# 2015_FDP_ACTIONNEUR.net
KiCad netlist of a schematic drawn in Altium Designer
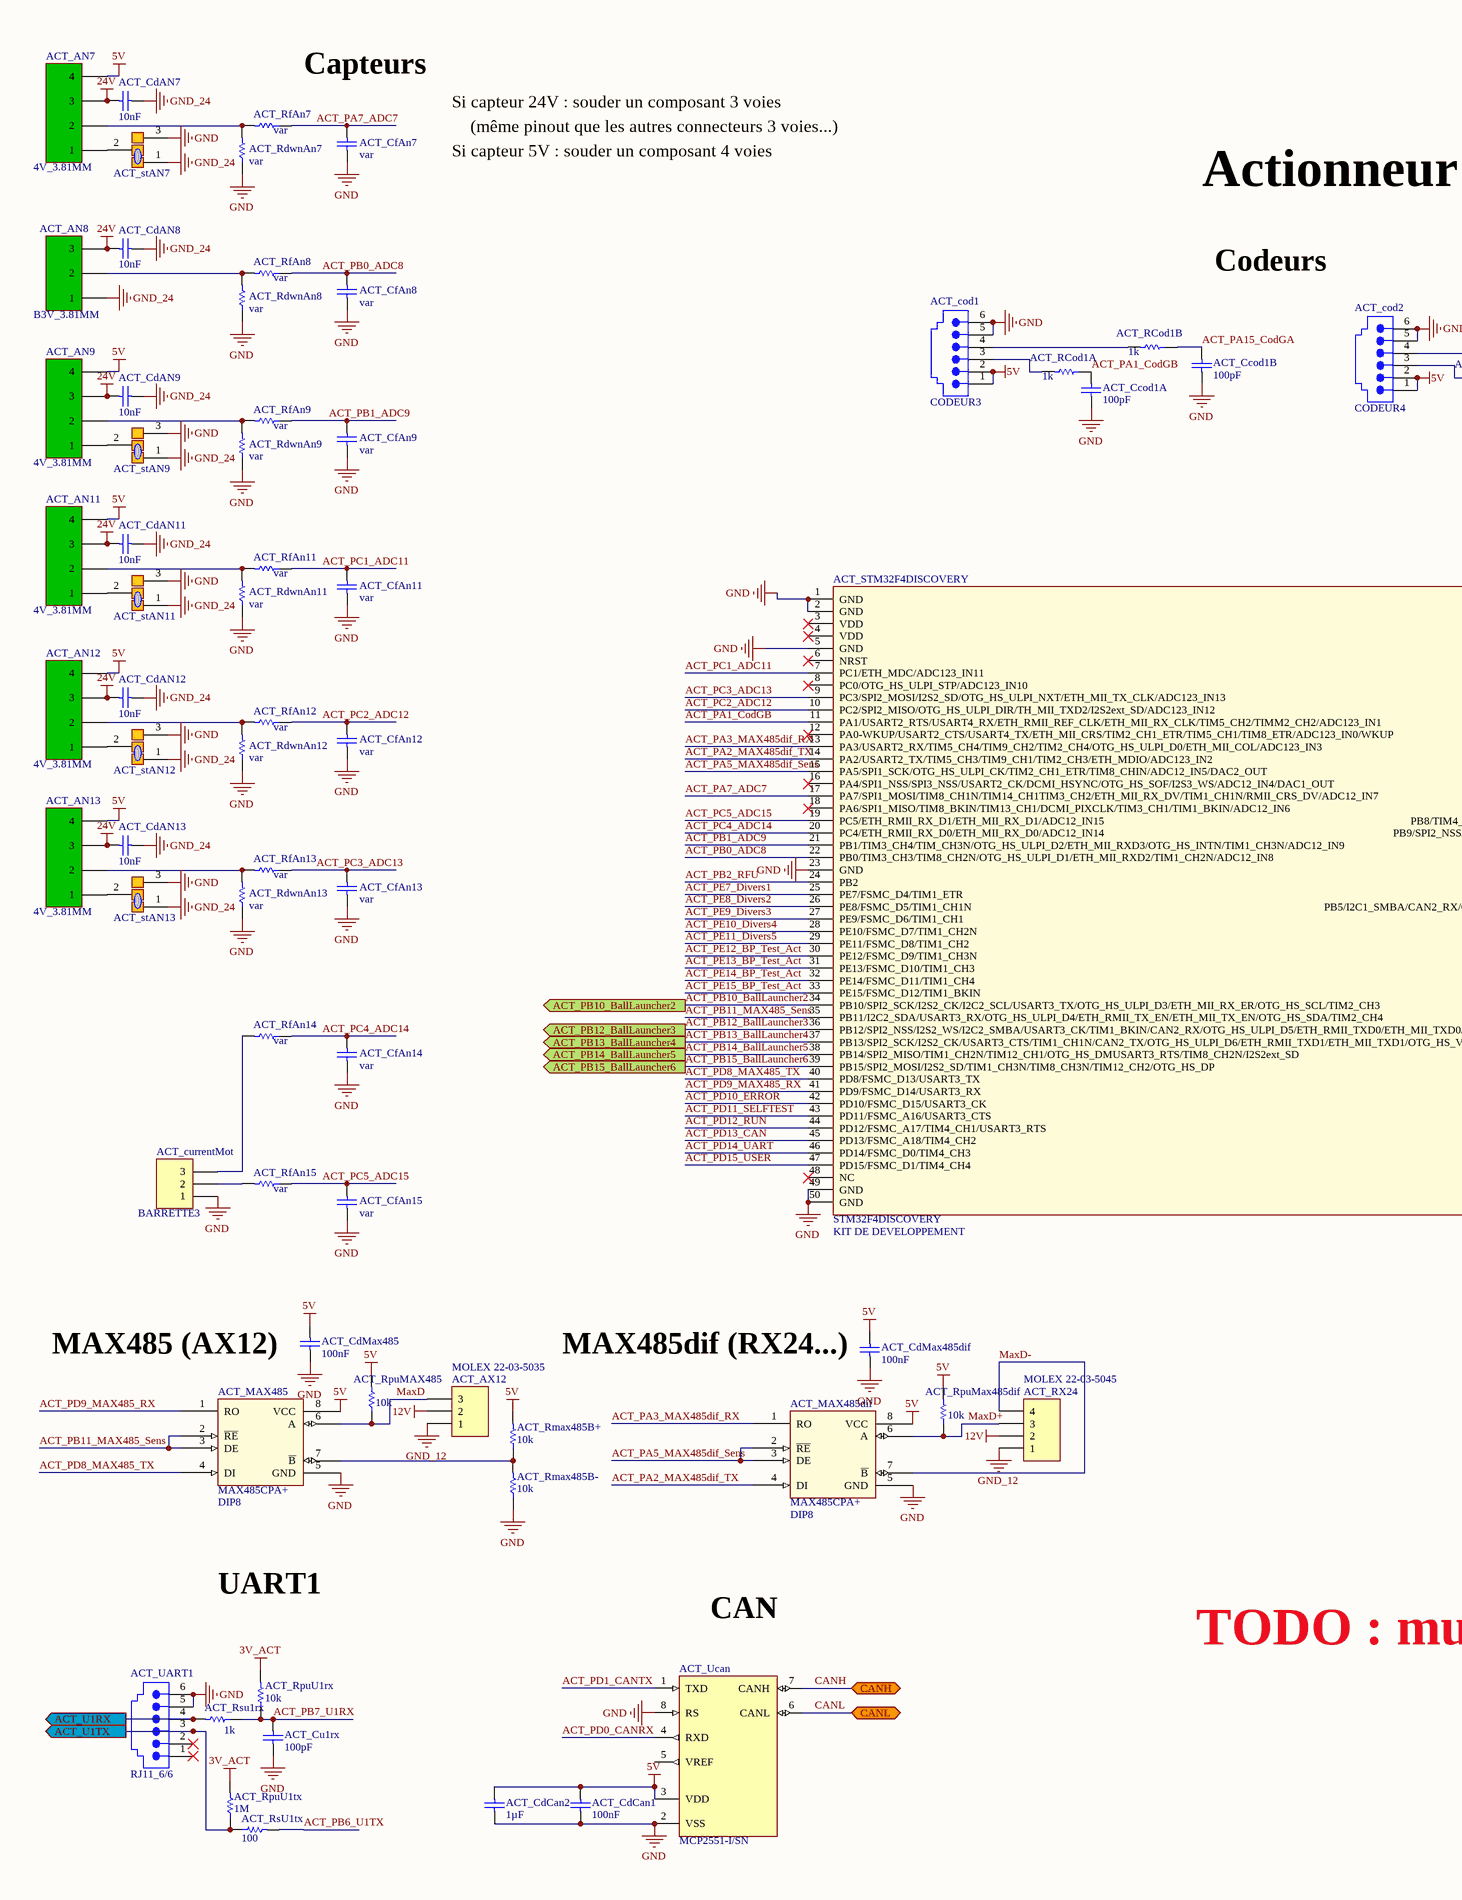
[diagram p0: 2015_FDP_ACTIONNEUR.SchDoc, left]
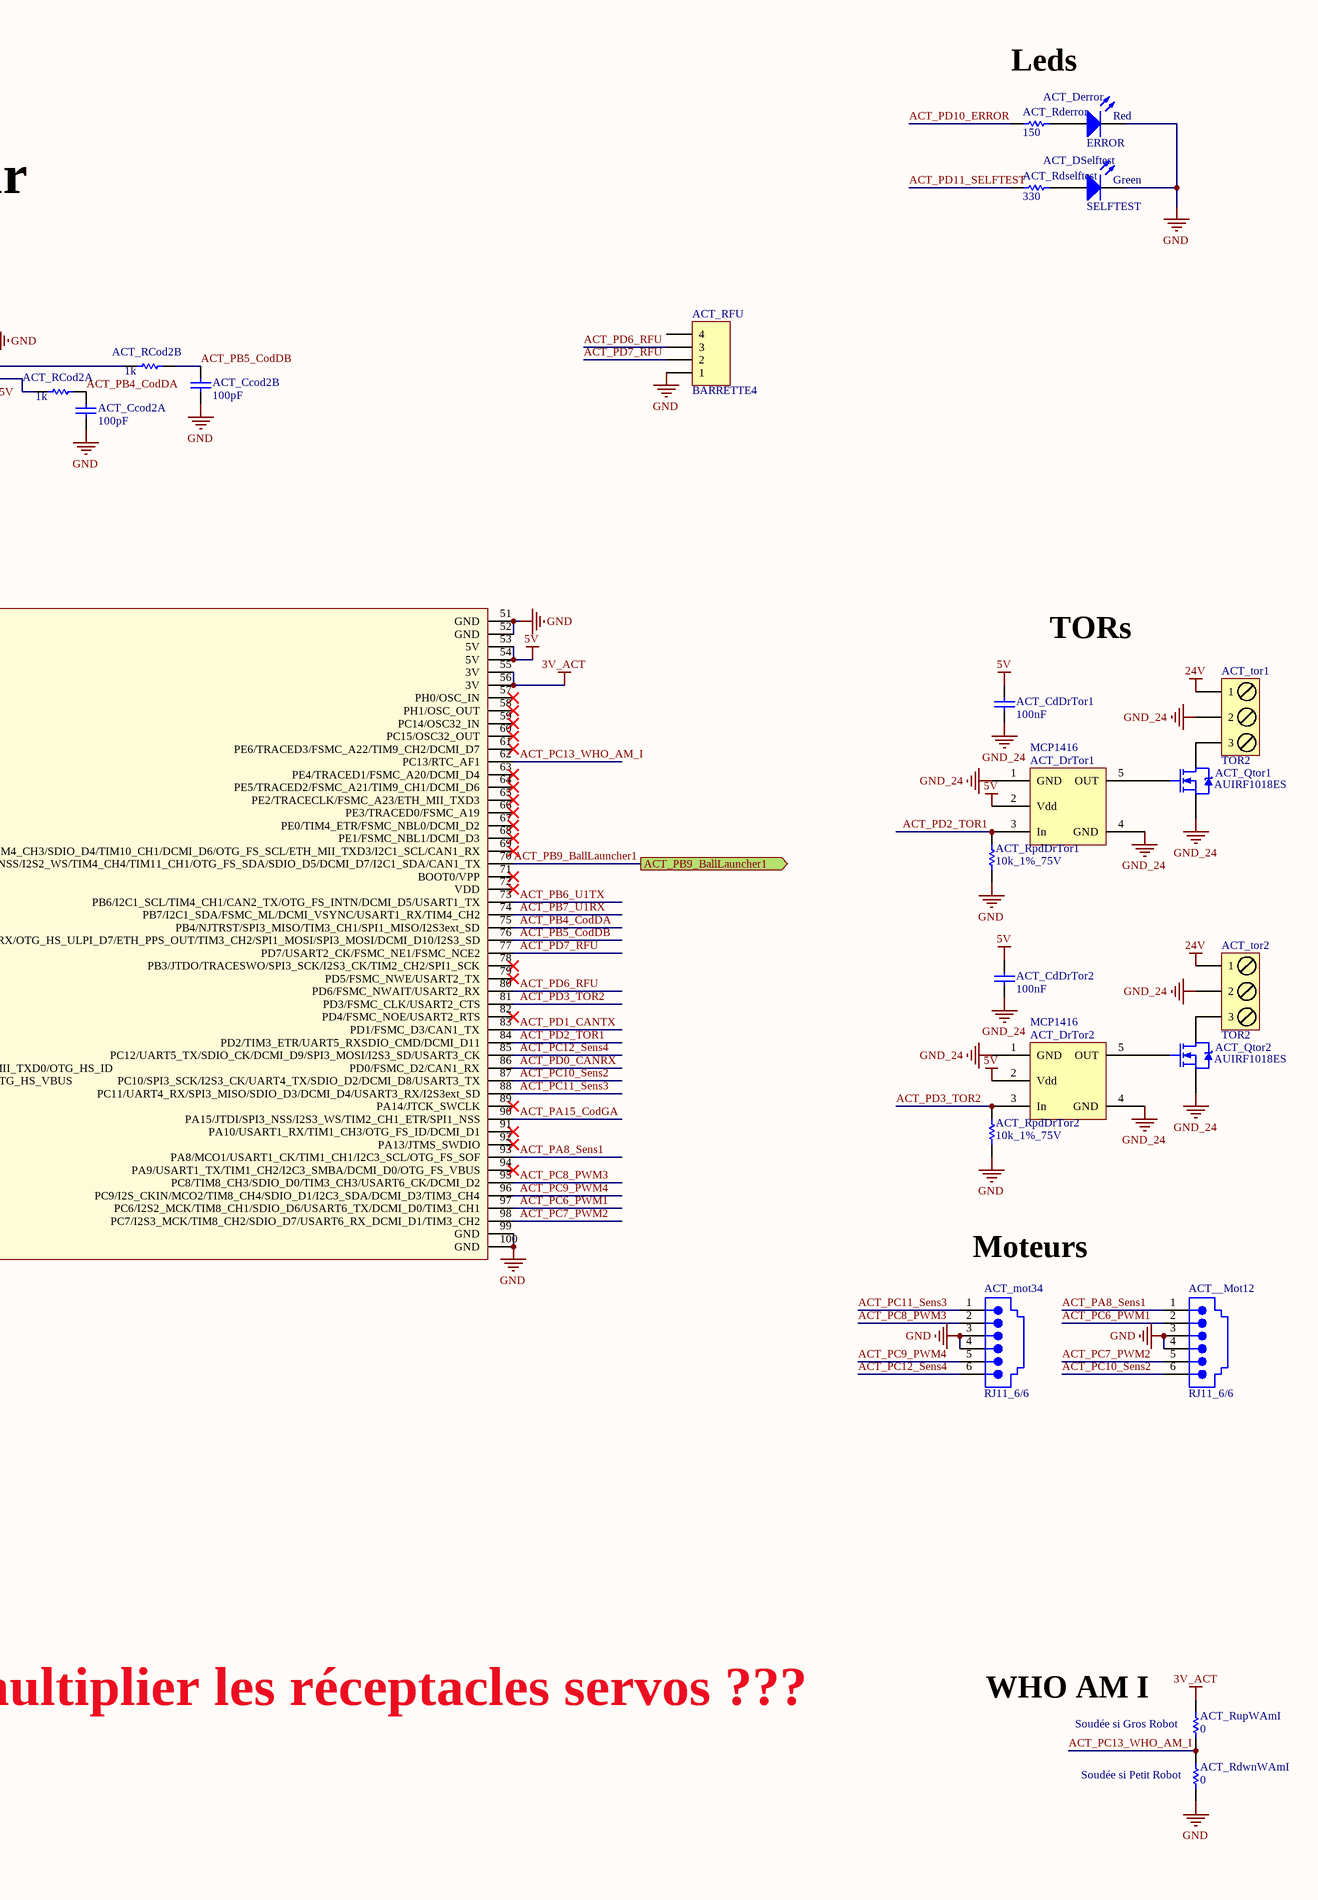
[diagram p1: 2015_FDP_ACTIONNEUR.SchDoc, right]

(export (version "E")
  (design (tool "Eeschema 10.0.6"))
  (components
    (comp (ref "ACT_AN7")
      (value "4V_3.81MM")
      (footprint "BORNIER_4V_3.81MM")
      (libsource (lib "Connecteur") (part "BORNIER_4V_3.81MM"))
    )
    (comp (ref "ACT_AN8")
      (value "B3V_3.81MM")
      (footprint "BORNIER_3V_3.81MM")
      (libsource (lib "Connecteur") (part "BORNIER_3V_3.81MM"))
    )
    (comp (ref "ACT_AN9")
      (value "4V_3.81MM")
      (footprint "BORNIER_4V_3.81MM")
      (libsource (lib "Connecteur") (part "BORNIER_4V_3.81MM"))
    )
    (comp (ref "ACT_AN11")
      (value "4V_3.81MM")
      (footprint "BORNIER_4V_3.81MM")
      (libsource (lib "Connecteur") (part "BORNIER_4V_3.81MM"))
    )
    (comp (ref "ACT_AN12")
      (value "4V_3.81MM")
      (footprint "BORNIER_4V_3.81MM")
      (libsource (lib "Connecteur") (part "BORNIER_4V_3.81MM"))
    )
    (comp (ref "ACT_AN13")
      (value "4V_3.81MM")
      (footprint "BORNIER_4V_3.81MM")
      (libsource (lib "Connecteur") (part "BORNIER_4V_3.81MM"))
    )
    (comp (ref "ACT_AX12")
      (value "MOLEX 22-03-5035")
      (footprint "MOLEX3_2.5MM")
      (description "Header, 3-Pin")
      (fields (field (name "PUBLISHER") "Altium Limited"))
      (libsource (lib "") (part "BARRETTE3_1"))
    )
    (comp (ref "ACT_Ccod1A")
      (value "100pF")
      (footprint "C0805_N")
      (description "Capacitor")
      (fields (field (name "PUBLISHER") "Altium Limited"))
      (libsource (lib "_ROBOT") (part "Condensateur"))
    )
    (comp (ref "ACT_Ccod1B")
      (value "100pF")
      (footprint "C0805_N")
      (description "Capacitor")
      (fields (field (name "PUBLISHER") "Altium Limited"))
      (libsource (lib "_ROBOT") (part "Condensateur"))
    )
    (comp (ref "ACT_Ccod2A")
      (value "100pF")
      (footprint "C0805_N")
      (description "Capacitor")
      (fields (field (name "PUBLISHER") "Altium Limited"))
      (libsource (lib "_ROBOT") (part "Condensateur"))
    )
    (comp (ref "ACT_Ccod2B")
      (value "100pF")
      (footprint "C0805_N")
      (description "Capacitor")
      (fields (field (name "PUBLISHER") "Altium Limited"))
      (libsource (lib "_ROBOT") (part "Condensateur"))
    )
    (comp (ref "ACT_CdAN7")
      (value "10nF")
      (footprint "C0805_N")
      (description "Capacitor")
      (fields (field (name "PUBLISHER") "Altium Limited"))
      (libsource (lib "_ROBOT") (part "Condensateur"))
    )
    (comp (ref "ACT_CdAN8")
      (value "10nF")
      (footprint "C0805_N")
      (description "Capacitor")
      (fields (field (name "PUBLISHER") "Altium Limited"))
      (libsource (lib "_ROBOT") (part "Condensateur"))
    )
    (comp (ref "ACT_CdAN9")
      (value "10nF")
      (footprint "C0805_N")
      (description "Capacitor")
      (fields (field (name "PUBLISHER") "Altium Limited"))
      (libsource (lib "_ROBOT") (part "Condensateur"))
    )
    (comp (ref "ACT_CdAN11")
      (value "10nF")
      (footprint "C0805_N")
      (description "Capacitor")
      (fields (field (name "PUBLISHER") "Altium Limited"))
      (libsource (lib "_ROBOT") (part "Condensateur"))
    )
    (comp (ref "ACT_CdAN12")
      (value "10nF")
      (footprint "C0805_N")
      (description "Capacitor")
      (fields (field (name "PUBLISHER") "Altium Limited"))
      (libsource (lib "_ROBOT") (part "Condensateur"))
    )
    (comp (ref "ACT_CdAN13")
      (value "10nF")
      (footprint "C0805_N")
      (description "Capacitor")
      (fields (field (name "PUBLISHER") "Altium Limited"))
      (libsource (lib "_ROBOT") (part "Condensateur"))
    )
    (comp (ref "ACT_CdCan1")
      (value "100nF")
      (footprint "C0805_N")
      (description "Capacitor")
      (fields (field (name "PUBLISHER") "Altium Limited"))
      (libsource (lib "_ROBOT") (part "Condensateur"))
    )
    (comp (ref "ACT_CdCan2")
      (value "1µF")
      (footprint "C0805_N")
      (description "Capacitor")
      (fields (field (name "PUBLISHER") "Altium Limited"))
      (libsource (lib "_ROBOT") (part "Condensateur"))
    )
    (comp (ref "ACT_CdDrTor1")
      (value "100nF")
      (footprint "C0805_N")
      (description "Capacitor")
      (fields (field (name "PUBLISHER") "Altium Limited"))
      (libsource (lib "DG_Condensateur") (part "Capacitor"))
    )
    (comp (ref "ACT_CdDrTor2")
      (value "100nF")
      (footprint "C0805_N")
      (description "Capacitor")
      (fields (field (name "PUBLISHER") "Altium Limited"))
      (libsource (lib "DG_Condensateur") (part "Capacitor"))
    )
    (comp (ref "ACT_CdMax485")
      (value "100nF")
      (footprint "C0805_N")
      (description "Capacitor")
      (fields (field (name "PUBLISHER") "Altium Limited"))
      (libsource (lib "_ROBOT") (part "Condensateur"))
    )
    (comp (ref "ACT_CdMax485dif")
      (value "100nF")
      (footprint "C0805_N")
      (description "Capacitor")
      (fields (field (name "PUBLISHER") "Altium Limited"))
      (libsource (lib "_ROBOT") (part "Condensateur"))
    )
    (comp (ref "ACT_CfAn7")
      (value "var")
      (footprint "C0805_N")
      (description "Capacitor")
      (fields (field (name "PUBLISHER") "Altium Limited"))
      (libsource (lib "_ROBOT") (part "Condensateur"))
    )
    (comp (ref "ACT_CfAn8")
      (value "var")
      (footprint "C0805_N")
      (description "Capacitor")
      (fields (field (name "PUBLISHER") "Altium Limited"))
      (libsource (lib "_ROBOT") (part "Condensateur"))
    )
    (comp (ref "ACT_CfAn9")
      (value "var")
      (footprint "C0805_N")
      (description "Capacitor")
      (fields (field (name "PUBLISHER") "Altium Limited"))
      (libsource (lib "_ROBOT") (part "Condensateur"))
    )
    (comp (ref "ACT_CfAn11")
      (value "var")
      (footprint "C0805_N")
      (description "Capacitor")
      (fields (field (name "PUBLISHER") "Altium Limited"))
      (libsource (lib "_ROBOT") (part "Condensateur"))
    )
    (comp (ref "ACT_CfAn12")
      (value "var")
      (footprint "C0805_N")
      (description "Capacitor")
      (fields (field (name "PUBLISHER") "Altium Limited"))
      (libsource (lib "_ROBOT") (part "Condensateur"))
    )
    (comp (ref "ACT_CfAn13")
      (value "var")
      (footprint "C0805_N")
      (description "Capacitor")
      (fields (field (name "PUBLISHER") "Altium Limited"))
      (libsource (lib "_ROBOT") (part "Condensateur"))
    )
    (comp (ref "ACT_CfAn14")
      (value "var")
      (footprint "C0805_N")
      (description "Capacitor")
      (fields (field (name "PUBLISHER") "Altium Limited"))
      (libsource (lib "_ROBOT") (part "Condensateur"))
    )
    (comp (ref "ACT_CfAn15")
      (value "var")
      (footprint "C0805_N")
      (description "Capacitor")
      (fields (field (name "PUBLISHER") "Altium Limited"))
      (libsource (lib "_ROBOT") (part "Condensateur"))
    )
    (comp (ref "ACT_cod1")
      (value "CODEUR3")
      (footprint "RJ11_6/6 - droit")
      (description "Right Angle, Standard Profile, Offset Latch DECconnect, Flangeless PCB Jack")
      (fields (field (name "PUBLISHER") "Altium Limited"))
      (libsource (lib "miniprojet") (part "RJ11_6/6"))
    )
    (comp (ref "ACT_cod2")
      (value "CODEUR4")
      (footprint "RJ11_6/6 - droit")
      (description "Right Angle, Standard Profile, Offset Latch DECconnect, Flangeless PCB Jack")
      (fields (field (name "PUBLISHER") "Altium Limited"))
      (libsource (lib "miniprojet") (part "RJ11_6/6"))
    )
    (comp (ref "ACT_Cu1rx")
      (value "100pF")
      (footprint "C0805_N")
      (description "Capacitor")
      (fields (field (name "PUBLISHER") "Altium Limited"))
      (libsource (lib "_ROBOT") (part "Condensateur"))
    )
    (comp (ref "ACT_currentMot")
      (value "BARRETTE3")
      (footprint "HE14_3")
      (description "Header, 3-Pin")
      (fields (field (name "PUBLISHER") "Altium Limited"))
      (libsource (lib "Connecteur") (part "BARRETTE3"))
    )
    (comp (ref "ACT_Derror")
      (value "ERROR")
      (footprint "LED_0805")
      (description "Typical LED")
      (fields (field (name "PUBLISHER") "Altium Limited"))
      (libsource (lib "_ROBOT") (part "LED"))
    )
    (comp (ref "ACT_DrTor1")
      (value "MCP1416")
      (footprint "SOT23-5AN")
      (libsource (lib "GAL") (part "MCP1402"))
    )
    (comp (ref "ACT_DrTor2")
      (value "MCP1416")
      (footprint "SOT23-5AN")
      (libsource (lib "GAL") (part "MCP1402"))
    )
    (comp (ref "ACT_DSelftest")
      (value "SELFTEST")
      (footprint "LED_0805")
      (description "Typical LED")
      (fields (field (name "PUBLISHER") "Altium Limited"))
      (libsource (lib "_ROBOT") (part "LED"))
    )
    (comp (ref "ACT_MAX485")
      (value "MAX485CPA+_DIP8")
      (footprint "SO8_N")
      (description "EMETTEUR/RECEPTEUR FAIBLE PUISSANCE DE LIAISONS RS422/RS485 - DIP8")
      (fields (field (name "TYPE") "MAX485CPA+") (field (name "PACKAGE") "DIP8"))
      (libsource (lib "circuits integres") (part "MAX485CPA+_DIP8"))
    )
    (comp (ref "ACT_MAX485dif")
      (value "MAX485CPA+_DIP8")
      (footprint "SO8_N")
      (description "EMETTEUR/RECEPTEUR FAIBLE PUISSANCE DE LIAISONS RS422/RS485 - DIP8")
      (fields (field (name "TYPE") "MAX485CPA+") (field (name "PACKAGE") "DIP8"))
      (libsource (lib "circuits integres") (part "MAX485CPA+_DIP8"))
    )
    (comp (ref "ACT_mot34")
      (value "RJ11_6/6")
      (footprint "RJ11_6/6")
      (description "Right Angle, Standard Profile, Offset Latch DECconnect, Flangeless PCB Jack")
      (fields (field (name "PUBLISHER") "Altium Limited"))
      (libsource (lib "Connecteur") (part "RJ11_6/6"))
    )
    (comp (ref "ACT_Qtor1")
      (value "AUIRF1018ES")
      (footprint "D2PAK")
      (description "HEXFET N-Channel Power MOSFET")
      (fields (field (name "PUBLISHER") "Altium Limited"))
      (libsource (lib "IR Discrete MOSFET - Power") (part "IRF1010S"))
    )
    (comp (ref "ACT_Qtor2")
      (value "AUIRF1018ES")
      (footprint "D2PAK")
      (description "HEXFET N-Channel Power MOSFET")
      (fields (field (name "PUBLISHER") "Altium Limited"))
      (libsource (lib "IR Discrete MOSFET - Power") (part "IRF1010S"))
    )
    (comp (ref "ACT_RCod1A")
      (value "1k")
      (footprint "R1206_N")
      (description "Resistor")
      (fields (field (name "PUBLISHER") "Altium Limited"))
      (libsource (lib "_ROBOT") (part "Resistor"))
    )
    (comp (ref "ACT_RCod1B")
      (value "1k")
      (footprint "R1206_N")
      (description "Resistor")
      (fields (field (name "PUBLISHER") "Altium Limited"))
      (libsource (lib "_ROBOT") (part "Resistor"))
    )
    (comp (ref "ACT_RCod2A")
      (value "1k")
      (footprint "R1206_N")
      (description "Resistor")
      (fields (field (name "PUBLISHER") "Altium Limited"))
      (libsource (lib "_ROBOT") (part "Resistor"))
    )
    (comp (ref "ACT_RCod2B")
      (value "1k")
      (footprint "R1206_N")
      (description "Resistor")
      (fields (field (name "PUBLISHER") "Altium Limited"))
      (libsource (lib "_ROBOT") (part "Resistor"))
    )
    (comp (ref "ACT_Rderror")
      (value "150")
      (footprint "R1206_N")
      (description "Resistor")
      (fields (field (name "PUBLISHER") "Altium Limited"))
      (libsource (lib "_ROBOT") (part "Resistor"))
    )
    (comp (ref "ACT_Rdselftest")
      (value "330")
      (footprint "R1206_N")
      (description "Resistor")
      (fields (field (name "PUBLISHER") "Altium Limited"))
      (libsource (lib "_ROBOT") (part "Resistor"))
    )
    (comp (ref "ACT_RdwnAn7")
      (value "var")
      (footprint "R1206_N")
      (description "Resistor")
      (fields (field (name "PUBLISHER") "Altium Limited"))
      (libsource (lib "_ROBOT") (part "Resistor"))
    )
    (comp (ref "ACT_RdwnAn8")
      (value "var")
      (footprint "R1206_N")
      (description "Resistor")
      (fields (field (name "PUBLISHER") "Altium Limited"))
      (libsource (lib "_ROBOT") (part "Resistor"))
    )
    (comp (ref "ACT_RdwnAn9")
      (value "var")
      (footprint "R1206_N")
      (description "Resistor")
      (fields (field (name "PUBLISHER") "Altium Limited"))
      (libsource (lib "_ROBOT") (part "Resistor"))
    )
    (comp (ref "ACT_RdwnAn11")
      (value "var")
      (footprint "R1206_N")
      (description "Resistor")
      (fields (field (name "PUBLISHER") "Altium Limited"))
      (libsource (lib "_ROBOT") (part "Resistor"))
    )
    (comp (ref "ACT_RdwnAn12")
      (value "var")
      (footprint "R1206_N")
      (description "Resistor")
      (fields (field (name "PUBLISHER") "Altium Limited"))
      (libsource (lib "_ROBOT") (part "Resistor"))
    )
    (comp (ref "ACT_RdwnAn13")
      (value "var")
      (footprint "R1206_N")
      (description "Resistor")
      (fields (field (name "PUBLISHER") "Altium Limited"))
      (libsource (lib "_ROBOT") (part "Resistor"))
    )
    (comp (ref "ACT_RdwnWAmI")
      (value "0")
      (footprint "R1206_N")
      (description "Resistor")
      (fields (field (name "PUBLISHER") "Altium Limited"))
      (libsource (lib "_ROBOT") (part "Resistor"))
    )
    (comp (ref "ACT_RfAn7")
      (value "var")
      (footprint "R1206_N")
      (description "Resistor")
      (fields (field (name "PUBLISHER") "Altium Limited"))
      (libsource (lib "_ROBOT") (part "Resistor"))
    )
    (comp (ref "ACT_RfAn8")
      (value "var")
      (footprint "R1206_N")
      (description "Resistor")
      (fields (field (name "PUBLISHER") "Altium Limited"))
      (libsource (lib "_ROBOT") (part "Resistor"))
    )
    (comp (ref "ACT_RfAn9")
      (value "var")
      (footprint "R1206_N")
      (description "Resistor")
      (fields (field (name "PUBLISHER") "Altium Limited"))
      (libsource (lib "_ROBOT") (part "Resistor"))
    )
    (comp (ref "ACT_RfAn11")
      (value "var")
      (footprint "R1206_N")
      (description "Resistor")
      (fields (field (name "PUBLISHER") "Altium Limited"))
      (libsource (lib "_ROBOT") (part "Resistor"))
    )
    (comp (ref "ACT_RfAn12")
      (value "var")
      (footprint "R1206_N")
      (description "Resistor")
      (fields (field (name "PUBLISHER") "Altium Limited"))
      (libsource (lib "_ROBOT") (part "Resistor"))
    )
    (comp (ref "ACT_RfAn13")
      (value "var")
      (footprint "R1206_N")
      (description "Resistor")
      (fields (field (name "PUBLISHER") "Altium Limited"))
      (libsource (lib "_ROBOT") (part "Resistor"))
    )
    (comp (ref "ACT_RfAn14")
      (value "var")
      (footprint "R1206_N")
      (description "Resistor")
      (fields (field (name "PUBLISHER") "Altium Limited"))
      (libsource (lib "_ROBOT") (part "Resistor"))
    )
    (comp (ref "ACT_RfAn15")
      (value "var")
      (footprint "R1206_N")
      (description "Resistor")
      (fields (field (name "PUBLISHER") "Altium Limited"))
      (libsource (lib "_ROBOT") (part "Resistor"))
    )
    (comp (ref "ACT_RFU")
      (value "BARRETTE4")
      (footprint "HE14_4")
      (description "Header, 4-Pin")
      (fields (field (name "PUBLISHER") "Altium Limited"))
      (libsource (lib "Connecteur") (part "BARRETTE4"))
    )
    (comp (ref "ACT_Rmax485B+")
      (value "10k")
      (footprint "R1206_N")
      (description "Resistor")
      (fields (field (name "PUBLISHER") "Altium Limited"))
      (libsource (lib "_ROBOT") (part "Resistor"))
    )
    (comp (ref "ACT_Rmax485B-")
      (value "10k")
      (footprint "R1206_N")
      (description "Resistor")
      (fields (field (name "PUBLISHER") "Altium Limited"))
      (libsource (lib "_ROBOT") (part "Resistor"))
    )
    (comp (ref "ACT_RpdDrTor1")
      (value "10k_1%_75V")
      (footprint "R1206_N")
      (description "Resistor")
      (fields (field (name "PUBLISHER") "Altium Limited"))
      (libsource (lib "DG_Resistance") (part "Resistor"))
    )
    (comp (ref "ACT_RpdDrTor2")
      (value "10k_1%_75V")
      (footprint "R1206_N")
      (description "Resistor")
      (fields (field (name "PUBLISHER") "Altium Limited"))
      (libsource (lib "DG_Resistance") (part "Resistor"))
    )
    (comp (ref "ACT_RpuMAX485")
      (value "10k")
      (footprint "R1206_N")
      (description "Resistor")
      (fields (field (name "PUBLISHER") "Altium Limited"))
      (libsource (lib "_ROBOT") (part "Resistor"))
    )
    (comp (ref "ACT_RpuMax485dif")
      (value "10k")
      (footprint "R1206_N")
      (description "Resistor")
      (fields (field (name "PUBLISHER") "Altium Limited"))
      (libsource (lib "_ROBOT") (part "Resistor"))
    )
    (comp (ref "ACT_RpuU1rx")
      (value "10k")
      (footprint "R1206_N")
      (description "Resistor")
      (fields (field (name "PUBLISHER") "Altium Limited"))
      (libsource (lib "_ROBOT") (part "Resistor"))
    )
    (comp (ref "ACT_RpuU1tx")
      (value "1M")
      (footprint "R1206_N")
      (description "Resistor")
      (fields (field (name "PUBLISHER") "Altium Limited"))
      (libsource (lib "_ROBOT") (part "Resistor"))
    )
    (comp (ref "ACT_Rsu1rx")
      (value "1k")
      (footprint "R1206_N")
      (description "Resistor")
      (fields (field (name "PUBLISHER") "Altium Limited"))
      (libsource (lib "_ROBOT") (part "Resistor"))
    )
    (comp (ref "ACT_RsU1tx")
      (value "100")
      (footprint "R1206_N")
      (description "Resistor")
      (fields (field (name "PUBLISHER") "Altium Limited"))
      (libsource (lib "_ROBOT") (part "Resistor"))
    )
    (comp (ref "ACT_RupWAmI")
      (value "0")
      (footprint "R1206_N")
      (description "Resistor")
      (fields (field (name "PUBLISHER") "Altium Limited"))
      (libsource (lib "_ROBOT") (part "Resistor"))
    )
    (comp (ref "ACT_RX24")
      (value "MOLEX 22-03-5045")
      (footprint "MOLEX4_2.5MM")
      (description "Header, 4-Pin")
      (fields (field (name "PUBLISHER") "Altium Limited"))
      (libsource (lib "Connecteur") (part "BARRETTE4"))
    )
    (comp (ref "ACT_stAN7")
      (value "strap")
      (footprint "Goutte Strap_3")
      (description "Goutte Strap_3")
      (fields (field (name "PUBLISHER") "Damien Guitton"))
      (libsource (lib "DG_Connecteur") (part "Goutte Strap_3"))
    )
    (comp (ref "ACT_stAN9")
      (value "strap")
      (footprint "Goutte Strap_3")
      (description "Goutte Strap_3")
      (fields (field (name "PUBLISHER") "Damien Guitton"))
      (libsource (lib "DG_Connecteur") (part "Goutte Strap_3"))
    )
    (comp (ref "ACT_stAN11")
      (value "strap")
      (footprint "Goutte Strap_3")
      (description "Goutte Strap_3")
      (fields (field (name "PUBLISHER") "Damien Guitton"))
      (libsource (lib "DG_Connecteur") (part "Goutte Strap_3"))
    )
    (comp (ref "ACT_stAN12")
      (value "strap")
      (footprint "Goutte Strap_3")
      (description "Goutte Strap_3")
      (fields (field (name "PUBLISHER") "Damien Guitton"))
      (libsource (lib "DG_Connecteur") (part "Goutte Strap_3"))
    )
    (comp (ref "ACT_stAN13")
      (value "strap")
      (footprint "Goutte Strap_3")
      (description "Goutte Strap_3")
      (fields (field (name "PUBLISHER") "Damien Guitton"))
      (libsource (lib "DG_Connecteur") (part "Goutte Strap_3"))
    )
    (comp (ref "ACT_STM32F4DISCOVERY")
      (value "STM32F4DISCOVERY")
      (footprint "STM32_F4DISCOVERY")
      (description "KIT DE DEVELOPPEMENT POUR MICROCONTROLEUR STM32F407VGT6")
      (fields (field (name "TYPE") "KIT DE DEVELOPPEMENT"))
      (libsource (lib "circuits integres") (part "STM32F4DISCOVERY"))
    )
    (comp (ref "ACT_tor1")
      (value "TOR2")
      (footprint "BORNIER3_FEM_COUDE")
      (description "Terminal blocks, 2 pins, pitch=5mm")
      (libsource (lib "miniprojet") (part "BORNIER3"))
    )
    (comp (ref "ACT_tor2")
      (value "TOR2")
      (footprint "BORNIER3_FEM_COUDE")
      (description "Terminal blocks, 2 pins, pitch=5mm")
      (libsource (lib "miniprojet") (part "BORNIER3"))
    )
    (comp (ref "ACT_UART1")
      (value "RJ11_6/6")
      (footprint "RJ11_6/6")
      (description "Right Angle, Standard Profile, Offset Latch DECconnect, Flangeless PCB Jack")
      (fields (field (name "PUBLISHER") "Altium Limited"))
      (libsource (lib "Connecteur") (part "RJ11_6/6"))
    )
    (comp (ref "ACT_Ucan")
      (value "MCP2551-I/SN")
      (footprint "SO8_N")
      (description "High-Speed CAN Transceiver, 8-Pin SOIC, Industrial Temperature")
      (fields (field (name "PUBLISHER") "Damien Guitton"))
      (libsource (lib "Circuit intégré") (part "MCP2551-I/SN"))
    )
    (comp (ref "ACT__Mot12")
      (value "RJ11_6/6")
      (footprint "RJ11_6/6")
      (description "Right Angle, Standard Profile, Offset Latch DECconnect, Flangeless PCB Jack")
      (fields (field (name "PUBLISHER") "Altium Limited"))
      (libsource (lib "Connecteur") (part "RJ11_6/6"))
    )
  )
  (nets
    (net (code "1") (name "/ACT_PA1_CodGB") (class "Default")
      (node (ref "ACT_Ccod1A") (pin "2") (pinfunction "2_2") (pintype "passive"))
      (node (ref "ACT_RCod1A") (pin "1") (pinfunction "1_1") (pintype "passive"))
      (node (ref "ACT_STM32F4DISCOVERY") (pin "11") (pinfunction "PA1/USART2_RTS/USART4_RX/ETH_RMII_REF_CLK/ETH_MII_RX_CLK/TIM5_CH2/TIMM2_CH2/ADC123_IN1_11") (pintype "passive"))
    )
    (net (code "2") (name "/ACT_PA2_MAX485dif_TX") (class "Default")
      (node (ref "ACT_MAX485dif") (pin "4") (pinfunction "DI_4") (pintype "input"))
      (node (ref "ACT_STM32F4DISCOVERY") (pin "14") (pinfunction "PA2/USART2_TX/TIM5_CH3/TIM9_CH1/TIM2_CH3/ETH_MDIO/ADC123_IN2_14") (pintype "passive"))
    )
    (net (code "3") (name "/ACT_PA3_MAX485dif_RX") (class "Default")
      (node (ref "ACT_MAX485dif") (pin "1") (pinfunction "RO_1") (pintype "tri_state"))
      (node (ref "ACT_STM32F4DISCOVERY") (pin "13") (pinfunction "PA3/USART2_RX/TIM5_CH4/TIM9_CH2/TIM2_CH4/OTG_HS_ULPI_D0/ETH_MII_COL/ADC123_IN3_13") (pintype "passive"))
    )
    (net (code "4") (name "/ACT_PA5_MAX485dif_Sens") (class "Default")
      (node (ref "ACT_MAX485dif") (pin "2") (pinfunction "~{RE}_2") (pintype "input"))
      (node (ref "ACT_MAX485dif") (pin "3") (pinfunction "DE_3") (pintype "input"))
      (node (ref "ACT_STM32F4DISCOVERY") (pin "15") (pinfunction "PA5/SPI1_SCK/OTG_HS_ULPI_CK/TIM2_CH1_ETR/TIM8_CHIN/ADC12_IN5/DAC2_OUT_15") (pintype "passive"))
    )
    (net (code "5") (name "/ACT_PA7_ADC7") (class "Default")
      (node (ref "ACT_CfAn7") (pin "2") (pinfunction "2_2") (pintype "passive"))
      (node (ref "ACT_RfAn7") (pin "1") (pinfunction "1_1") (pintype "passive"))
      (node (ref "ACT_STM32F4DISCOVERY") (pin "17") (pinfunction "PA7/SPI1_MOSI/TIM8_CH1N/TIM14_CH1TIM3_CH2/ETH_MII_RX_DV/TIM1_CH1N/RMII_CRS_DV/ADC12_IN7_17") (pintype "passive"))
    )
    (net (code "6") (name "/ACT_PA8_Sens1") (class "Default")
      (node (ref "ACT_STM32F4DISCOVERY") (pin "93") (pinfunction "PA8/MCO1/USART1_CK/TIM1_CH1/I2C3_SCL/OTG_FS_SOF_93") (pintype "passive"))
      (node (ref "ACT__Mot12") (pin "1") (pinfunction "1_1") (pintype "passive"))
    )
    (net (code "7") (name "/ACT_PA15_CodGA") (class "Default")
      (node (ref "ACT_Ccod1B") (pin "2") (pinfunction "2_2") (pintype "passive"))
      (node (ref "ACT_RCod1B") (pin "1") (pinfunction "1_1") (pintype "passive"))
      (node (ref "ACT_STM32F4DISCOVERY") (pin "90") (pinfunction "PA15/JTDI/SPI3_NSS/I2S3_WS/TIM2_CH1_ETR/SPI1_NSS_90") (pintype "passive"))
    )
    (net (code "8") (name "/ACT_PB0_ADC8") (class "Default")
      (node (ref "ACT_CfAn8") (pin "2") (pinfunction "2_2") (pintype "passive"))
      (node (ref "ACT_RfAn8") (pin "1") (pinfunction "1_1") (pintype "passive"))
      (node (ref "ACT_STM32F4DISCOVERY") (pin "22") (pinfunction "PB0/TIM3_CH3/TIM8_CH2N/OTG_HS_ULPI_D1/ETH_MII_RXD2/TIM1_CH2N/ADC12_IN8_22") (pintype "passive"))
    )
    (net (code "9") (name "/ACT_PB1_ADC9") (class "Default")
      (node (ref "ACT_CfAn9") (pin "2") (pinfunction "2_2") (pintype "passive"))
      (node (ref "ACT_RfAn9") (pin "1") (pinfunction "1_1") (pintype "passive"))
      (node (ref "ACT_STM32F4DISCOVERY") (pin "21") (pinfunction "PB1/TIM3_CH4/TIM_CH3N/OTG_HS_ULPI_D2/ETH_MII_RXD3/OTG_HS_INTN/TIM1_CH3N/ADC12_IN9_21") (pintype "passive"))
    )
    (net (code "10") (name "/ACT_PB2_RFU") (class "Default")
      (node (ref "ACT_STM32F4DISCOVERY") (pin "24") (pinfunction "PB2_24") (pintype "passive"))
    )
    (net (code "11") (name "/ACT_PB4_CodDA") (class "Default")
      (node (ref "ACT_Ccod2A") (pin "2") (pinfunction "2_2") (pintype "passive"))
      (node (ref "ACT_RCod2A") (pin "1") (pinfunction "1_1") (pintype "passive"))
      (node (ref "ACT_STM32F4DISCOVERY") (pin "75") (pinfunction "PB4/NJTRST/SPI3_MISO/TIM3_CH1/SPI1_MISO/I2S3ext_SD_75") (pintype "passive"))
    )
    (net (code "12") (name "/ACT_PB5_CodDB") (class "Default")
      (node (ref "ACT_Ccod2B") (pin "2") (pinfunction "2_2") (pintype "passive"))
      (node (ref "ACT_RCod2B") (pin "1") (pinfunction "1_1") (pintype "passive"))
      (node (ref "ACT_STM32F4DISCOVERY") (pin "76") (pinfunction "PB5/I2C1_SMBA/CAN2_RX/OTG_HS_ULPI_D7/ETH_PPS_OUT/TIM3_CH2/SPI1_MOSI/SPI3_MOSI/DCMI_D10/I2S3_SD_76") (pintype "passive"))
    )
    (net (code "13") (name "/ACT_PB6_U1TX") (class "Default")
      (node (ref "ACT_RsU1tx") (pin "2") (pinfunction "2_2") (pintype "passive"))
      (node (ref "ACT_STM32F4DISCOVERY") (pin "73") (pinfunction "PB6/I2C1_SCL/TIM4_CH1/CAN2_TX/OTG_FS_INTN/DCMI_D5/USART1_TX_73") (pintype "passive"))
    )
    (net (code "14") (name "/ACT_PB7_U1RX") (class "Default")
      (node (ref "ACT_Cu1rx") (pin "2") (pinfunction "2_2") (pintype "passive"))
      (node (ref "ACT_RpuU1rx") (pin "1") (pinfunction "1_1") (pintype "passive"))
      (node (ref "ACT_Rsu1rx") (pin "1") (pinfunction "1_1") (pintype "passive"))
      (node (ref "ACT_STM32F4DISCOVERY") (pin "74") (pinfunction "PB7/I2C1_SDA/FSMC_ML/DCMI_VSYNC/USART1_RX/TIM4_CH2_74") (pintype "passive"))
    )
    (net (code "15") (name "/ACT_PB9_BallLauncher1") (class "Default")
      (node (ref "ACT_STM32F4DISCOVERY") (pin "70") (pinfunction "PB9/SPI2_NSS/I2S2_WS/TIM4_CH4/TIM11_CH1/OTG_FS_SDA/SDIO_D5/DCMI_D7/I2C1_SDA/CAN1_TX_70") (pintype "passive"))
    )
    (net (code "16") (name "/ACT_PB10_BallLauncher2") (class "Default")
      (node (ref "ACT_STM32F4DISCOVERY") (pin "34") (pinfunction "PB10/SPI2_SCK/I2S2_CK/I2C2_SCL/USART3_TX/OTG_HS_ULPI_D3/ETH_MII_RX_ER/OTG_HS_SCL/TIM2_CH3_34") (pintype "passive"))
    )
    (net (code "17") (name "/ACT_PB11_MAX485_Sens") (class "Default")
      (node (ref "ACT_MAX485") (pin "2") (pinfunction "~{RE}_2") (pintype "input"))
      (node (ref "ACT_MAX485") (pin "3") (pinfunction "DE_3") (pintype "input"))
      (node (ref "ACT_STM32F4DISCOVERY") (pin "35") (pinfunction "PB11/I2C2_SDA/USART3_RX/OTG_HS_ULPI_D4/ETH_RMII_TX_EN/ETH_MII_TX_EN/OTG_HS_SDA/TIM2_CH4_35") (pintype "passive"))
    )
    (net (code "18") (name "/ACT_PB12_BallLauncher3") (class "Default")
      (node (ref "ACT_STM32F4DISCOVERY") (pin "36") (pinfunction "PB12/SPI2_NSS/I2S2_WS/I2C2_SMBA/USART3_CK/TIM1_BKIN/CAN2_RX/OTG_HS_ULPI_D5/ETH_RMII_TXD0/ETH_MII_TXD0/OTG_HS_ID_36") (pintype "passive"))
    )
    (net (code "19") (name "/ACT_PB13_BallLauncher4") (class "Default")
      (node (ref "ACT_STM32F4DISCOVERY") (pin "37") (pinfunction "PB13/SPI2_SCK/I2S2_CK/USART3_CTS/TIM1_CH1N/CAN2_TX/OTG_HS_ULPI_D6/ETH_RMII_TXD1/ETH_MII_TXD1/OTG_HS_VBUS_37") (pintype "passive"))
    )
    (net (code "20") (name "/ACT_PB14_BallLauncher5") (class "Default")
      (node (ref "ACT_STM32F4DISCOVERY") (pin "38") (pinfunction "PB14/SPI2_MISO/TIM1_CH2N/TIM12_CH1/OTG_HS_DMUSART3_RTS/TIM8_CH2N/I2S2ext_SD_38") (pintype "passive"))
    )
    (net (code "21") (name "/ACT_PB15_BallLauncher6") (class "Default")
      (node (ref "ACT_STM32F4DISCOVERY") (pin "39") (pinfunction "PB15/SPI2_MOSI/I2S2_SD/TIM1_CH3N/TIM8_CH3N/TIM12_CH2/OTG_HS_DP_39") (pintype "passive"))
    )
    (net (code "22") (name "/ACT_PC1_ADC11") (class "Default")
      (node (ref "ACT_CfAn11") (pin "2") (pinfunction "2_2") (pintype "passive"))
      (node (ref "ACT_RfAn11") (pin "1") (pinfunction "1_1") (pintype "passive"))
      (node (ref "ACT_STM32F4DISCOVERY") (pin "7") (pinfunction "PC1/ETH_MDC/ADC123_IN11_7") (pintype "passive"))
    )
    (net (code "23") (name "/ACT_PC2_ADC12") (class "Default")
      (node (ref "ACT_CfAn12") (pin "2") (pinfunction "2_2") (pintype "passive"))
      (node (ref "ACT_RfAn12") (pin "1") (pinfunction "1_1") (pintype "passive"))
      (node (ref "ACT_STM32F4DISCOVERY") (pin "10") (pinfunction "PC2/SPI2_MISO/OTG_HS_ULPI_DIR/TH_MII_TXD2/I2S2ext_SD/ADC123_IN12_10") (pintype "passive"))
    )
    (net (code "24") (name "/ACT_PC3_ADC13") (class "Default")
      (node (ref "ACT_CfAn13") (pin "2") (pinfunction "2_2") (pintype "passive"))
      (node (ref "ACT_RfAn13") (pin "1") (pinfunction "1_1") (pintype "passive"))
      (node (ref "ACT_STM32F4DISCOVERY") (pin "9") (pinfunction "PC3/SPI2_MOSI/I2S2_SD/OTG_HS_ULPI_NXT/ETH_MII_TX_CLK/ADC123_IN13_9") (pintype "passive"))
    )
    (net (code "25") (name "/ACT_PC4_ADC14") (class "Default")
      (node (ref "ACT_CfAn14") (pin "2") (pinfunction "2_2") (pintype "passive"))
      (node (ref "ACT_RfAn14") (pin "1") (pinfunction "1_1") (pintype "passive"))
      (node (ref "ACT_STM32F4DISCOVERY") (pin "20") (pinfunction "PC4/ETH_RMII_RX_D0/ETH_MII_RX_D0/ADC12_IN14_20") (pintype "passive"))
    )
    (net (code "26") (name "/ACT_PC5_ADC15") (class "Default")
      (node (ref "ACT_CfAn15") (pin "2") (pinfunction "2_2") (pintype "passive"))
      (node (ref "ACT_RfAn15") (pin "1") (pinfunction "1_1") (pintype "passive"))
      (node (ref "ACT_STM32F4DISCOVERY") (pin "19") (pinfunction "PC5/ETH_RMII_RX_D1/ETH_MII_RX_D1/ADC12_IN15_19") (pintype "passive"))
    )
    (net (code "27") (name "/ACT_PC6_PWM1") (class "Default")
      (node (ref "ACT_STM32F4DISCOVERY") (pin "97") (pinfunction "PC6/I2S2_MCK/TIM8_CH1/SDIO_D6/USART6_TX/DCMI_D0/TIM3_CH1_97") (pintype "passive"))
      (node (ref "ACT__Mot12") (pin "2") (pinfunction "2_2") (pintype "passive"))
    )
    (net (code "28") (name "/ACT_PC7_PWM2") (class "Default")
      (node (ref "ACT_STM32F4DISCOVERY") (pin "98") (pinfunction "PC7/I2S3_MCK/TIM8_CH2/SDIO_D7/USART6_RX_DCMI_D1/TIM3_CH2_98") (pintype "passive"))
      (node (ref "ACT__Mot12") (pin "5") (pinfunction "5_5") (pintype "passive"))
    )
    (net (code "29") (name "/ACT_PC8_PWM3") (class "Default")
      (node (ref "ACT_STM32F4DISCOVERY") (pin "95") (pinfunction "PC8/TIM8_CH3/SDIO_D0/TIM3_CH3/USART6_CK/DCMI_D2_95") (pintype "passive"))
      (node (ref "ACT_mot34") (pin "2") (pinfunction "2_2") (pintype "passive"))
    )
    (net (code "30") (name "/ACT_PC9_PWM4") (class "Default")
      (node (ref "ACT_STM32F4DISCOVERY") (pin "96") (pinfunction "PC9/I2S_CKIN/MCO2/TIM8_CH4/SDIO_D1/I2C3_SDA/DCMI_D3/TIM3_CH4_96") (pintype "passive"))
      (node (ref "ACT_mot34") (pin "5") (pinfunction "5_5") (pintype "passive"))
    )
    (net (code "31") (name "/ACT_PC10_Sens2") (class "Default")
      (node (ref "ACT_STM32F4DISCOVERY") (pin "87") (pinfunction "PC10/SPI3_SCK/I2S3_CK/UART4_TX/SDIO_D2/DCMI_D8/USART3_TX_87") (pintype "passive"))
      (node (ref "ACT__Mot12") (pin "6") (pinfunction "6_6") (pintype "passive"))
    )
    (net (code "32") (name "/ACT_PC11_Sens3") (class "Default")
      (node (ref "ACT_STM32F4DISCOVERY") (pin "88") (pinfunction "PC11/UART4_RX/SPI3_MISO/SDIO_D3/DCMI_D4/USART3_RX/I2S3ext_SD_88") (pintype "passive"))
      (node (ref "ACT_mot34") (pin "1") (pinfunction "1_1") (pintype "passive"))
    )
    (net (code "33") (name "/ACT_PC12_Sens4") (class "Default")
      (node (ref "ACT_STM32F4DISCOVERY") (pin "85") (pinfunction "PC12/UART5_TX/SDIO_CK/DCMI_D9/SPI3_MOSI/I2S3_SD/USART3_CK_85") (pintype "passive"))
      (node (ref "ACT_mot34") (pin "6") (pinfunction "6_6") (pintype "passive"))
    )
    (net (code "34") (name "/ACT_PC13_WHO_AM_I") (class "Default")
      (node (ref "ACT_RdwnWAmI") (pin "2") (pinfunction "2_2") (pintype "passive"))
      (node (ref "ACT_RupWAmI") (pin "1") (pinfunction "1_1") (pintype "passive"))
      (node (ref "ACT_STM32F4DISCOVERY") (pin "62") (pinfunction "PC13/RTC_AF1_62") (pintype "passive"))
    )
    (net (code "35") (name "/ACT_PD0_CANRX") (class "Default")
      (node (ref "ACT_STM32F4DISCOVERY") (pin "86") (pinfunction "PD0/FSMC_D2/CAN1_RX_86") (pintype "passive"))
      (node (ref "ACT_Ucan") (pin "4") (pinfunction "RXD_4") (pintype "output"))
    )
    (net (code "36") (name "/ACT_PD1_CANTX") (class "Default")
      (node (ref "ACT_STM32F4DISCOVERY") (pin "83") (pinfunction "PD1/FSMC_D3/CAN1_TX_83") (pintype "passive"))
      (node (ref "ACT_Ucan") (pin "1") (pinfunction "TXD_1") (pintype "input"))
    )
    (net (code "37") (name "/ACT_PD2_TOR1") (class "Default")
      (node (ref "ACT_DrTor1") (pin "3") (pinfunction "In_3") (pintype "passive"))
      (node (ref "ACT_RpdDrTor1") (pin "2") (pinfunction "2_2") (pintype "passive"))
      (node (ref "ACT_STM32F4DISCOVERY") (pin "84") (pinfunction "PD2/TIM3_ETR/UART5_RXSDIO_CMD/DCMI_D11_84") (pintype "passive"))
    )
    (net (code "38") (name "/ACT_PD3_TOR2") (class "Default")
      (node (ref "ACT_DrTor2") (pin "3") (pinfunction "In_3") (pintype "passive"))
      (node (ref "ACT_RpdDrTor2") (pin "2") (pinfunction "2_2") (pintype "passive"))
      (node (ref "ACT_STM32F4DISCOVERY") (pin "81") (pinfunction "PD3/FSMC_CLK/USART2_CTS_81") (pintype "passive"))
    )
    (net (code "39") (name "/ACT_PD6_RFU") (class "Default")
      (node (ref "ACT_RFU") (pin "3") (pinfunction "3_3") (pintype "passive"))
      (node (ref "ACT_STM32F4DISCOVERY") (pin "80") (pinfunction "PD6/FSMC_NWAIT/USART2_RX_80") (pintype "passive"))
    )
    (net (code "40") (name "/ACT_PD7_RFU") (class "Default")
      (node (ref "ACT_RFU") (pin "2") (pinfunction "2_2") (pintype "passive"))
      (node (ref "ACT_STM32F4DISCOVERY") (pin "77") (pinfunction "PD7/USART2_CK/FSMC_NE1/FSMC_NCE2_77") (pintype "passive"))
    )
    (net (code "41") (name "/ACT_PD8_MAX485_TX") (class "Default")
      (node (ref "ACT_MAX485") (pin "4") (pinfunction "DI_4") (pintype "input"))
      (node (ref "ACT_STM32F4DISCOVERY") (pin "40") (pinfunction "PD8/FSMC_D13/USART3_TX_40") (pintype "passive"))
    )
    (net (code "42") (name "/ACT_PD9_MAX485_RX") (class "Default")
      (node (ref "ACT_MAX485") (pin "1") (pinfunction "RO_1") (pintype "tri_state"))
      (node (ref "ACT_STM32F4DISCOVERY") (pin "41") (pinfunction "PD9/FSMC_D14/USART3_RX_41") (pintype "passive"))
    )
    (net (code "43") (name "/ACT_PD10_ERROR") (class "Default")
      (node (ref "ACT_Rderror") (pin "1") (pinfunction "1_1") (pintype "passive"))
      (node (ref "ACT_STM32F4DISCOVERY") (pin "42") (pinfunction "PD10/FSMC_D15/USART3_CK_42") (pintype "passive"))
    )
    (net (code "44") (name "/ACT_PD11_SELFTEST") (class "Default")
      (node (ref "ACT_Rdselftest") (pin "1") (pinfunction "1_1") (pintype "passive"))
      (node (ref "ACT_STM32F4DISCOVERY") (pin "43") (pinfunction "PD11/FSMC_A16/USART3_CTS_43") (pintype "passive"))
    )
    (net (code "45") (name "/ACT_PD12_RUN") (class "Default")
      (node (ref "ACT_STM32F4DISCOVERY") (pin "44") (pinfunction "PD12/FSMC_A17/TIM4_CH1/USART3_RTS_44") (pintype "passive"))
    )
    (net (code "46") (name "/ACT_PD13_CAN") (class "Default")
      (node (ref "ACT_STM32F4DISCOVERY") (pin "45") (pinfunction "PD13/FSMC_A18/TIM4_CH2_45") (pintype "passive"))
    )
    (net (code "47") (name "/ACT_PD14_UART") (class "Default")
      (node (ref "ACT_STM32F4DISCOVERY") (pin "46") (pinfunction "PD14/FSMC_D0/TIM4_CH3_46") (pintype "passive"))
    )
    (net (code "48") (name "/ACT_PD15_USER") (class "Default")
      (node (ref "ACT_STM32F4DISCOVERY") (pin "47") (pinfunction "PD15/FSMC_D1/TIM4_CH4_47") (pintype "passive"))
    )
    (net (code "49") (name "/ACT_PE7_Divers1") (class "Default")
      (node (ref "ACT_STM32F4DISCOVERY") (pin "25") (pinfunction "PE7/FSMC_D4/TIM1_ETR_25") (pintype "passive"))
    )
    (net (code "50") (name "/ACT_PE8_Divers2") (class "Default")
      (node (ref "ACT_STM32F4DISCOVERY") (pin "26") (pinfunction "PE8/FSMC_D5/TIM1_CH1N_26") (pintype "passive"))
    )
    (net (code "51") (name "/ACT_PE9_Divers3") (class "Default")
      (node (ref "ACT_STM32F4DISCOVERY") (pin "27") (pinfunction "PE9/FSMC_D6/TIM1_CH1_27") (pintype "passive"))
    )
    (net (code "52") (name "/ACT_PE10_Divers4") (class "Default")
      (node (ref "ACT_STM32F4DISCOVERY") (pin "28") (pinfunction "PE10/FSMC_D7/TIM1_CH2N_28") (pintype "passive"))
    )
    (net (code "53") (name "/ACT_PE11_Divers5") (class "Default")
      (node (ref "ACT_STM32F4DISCOVERY") (pin "29") (pinfunction "PE11/FSMC_D8/TIM1_CH2_29") (pintype "passive"))
    )
    (net (code "54") (name "/ACT_PE12_BP_Test_Act") (class "Default")
      (node (ref "ACT_STM32F4DISCOVERY") (pin "30") (pinfunction "PE12/FSMC_D9/TIM1_CH3N_30") (pintype "passive"))
    )
    (net (code "55") (name "/ACT_PE13_BP_Test_Act") (class "Default")
      (node (ref "ACT_STM32F4DISCOVERY") (pin "31") (pinfunction "PE13/FSMC_D10/TIM1_CH3_31") (pintype "passive"))
    )
    (net (code "56") (name "/ACT_PE14_BP_Test_Act") (class "Default")
      (node (ref "ACT_STM32F4DISCOVERY") (pin "32") (pinfunction "PE14/FSMC_D11/TIM1_CH4_32") (pintype "passive"))
    )
    (net (code "57") (name "/ACT_PE15_BP_Test_Act") (class "Default")
      (node (ref "ACT_STM32F4DISCOVERY") (pin "33") (pinfunction "PE15/FSMC_D12/TIM1_BKIN_33") (pintype "passive"))
    )
    (net (code "58") (name "/ACT_U1RX") (class "Default")
      (node (ref "ACT_Rsu1rx") (pin "2") (pinfunction "2_2") (pintype "passive"))
      (node (ref "ACT_UART1") (pin "4") (pinfunction "4_4") (pintype "passive"))
    )
    (net (code "59") (name "/ACT_U1TX") (class "Default")
      (node (ref "ACT_RpuU1tx") (pin "1") (pinfunction "1_1") (pintype "passive"))
      (node (ref "ACT_RsU1tx") (pin "1") (pinfunction "1_1") (pintype "passive"))
      (node (ref "ACT_UART1") (pin "3") (pinfunction "3_3") (pintype "passive"))
    )
    (net (code "60") (name "/CANH") (class "Default")
      (node (ref "ACT_Ucan") (pin "7") (pinfunction "CANH_7") (pintype "bidirectional"))
    )
    (net (code "61") (name "/CANL") (class "Default")
      (node (ref "ACT_Ucan") (pin "6") (pinfunction "CANL_6") (pintype "bidirectional"))
    )
    (net (code "62") (name "/MaxD") (class "Default")
      (node (ref "ACT_AX12") (pin "3") (pinfunction "3_3") (pintype "passive"))
      (node (ref "ACT_MAX485") (pin "6") (pinfunction "A_6") (pintype "bidirectional"))
      (node (ref "ACT_RpuMAX485") (pin "1") (pinfunction "1_1") (pintype "passive"))
    )
    (net (code "63") (name "/MaxD+") (class "Default")
      (node (ref "ACT_MAX485dif") (pin "6") (pinfunction "A_6") (pintype "bidirectional"))
      (node (ref "ACT_RX24") (pin "3") (pinfunction "3_3") (pintype "passive"))
      (node (ref "ACT_RpuMax485dif") (pin "1") (pinfunction "1_1") (pintype "passive"))
    )
    (net (code "64") (name "/MaxD-") (class "Default")
      (node (ref "ACT_MAX485dif") (pin "7") (pinfunction "~{B}_7") (pintype "bidirectional"))
      (node (ref "ACT_RX24") (pin "4") (pinfunction "4_4") (pintype "passive"))
    )
    (net (code "65") (name "3V_ACT") (class "Default")
      (node (ref "ACT_RpuU1rx") (pin "2") (pinfunction "2_2") (pintype "passive"))
      (node (ref "ACT_RpuU1tx") (pin "2") (pinfunction "2_2") (pintype "passive"))
      (node (ref "ACT_RupWAmI") (pin "2") (pinfunction "2_2") (pintype "passive"))
      (node (ref "ACT_STM32F4DISCOVERY") (pin "55") (pinfunction "3V_55") (pintype "passive"))
      (node (ref "ACT_STM32F4DISCOVERY") (pin "56") (pinfunction "3V_56") (pintype "passive"))
    )
    (net (code "66") (name "5V") (class "Default")
      (node (ref "ACT_AN11") (pin "4") (pinfunction "4_4") (pintype "passive"))
      (node (ref "ACT_AN12") (pin "4") (pinfunction "4_4") (pintype "passive"))
      (node (ref "ACT_AN13") (pin "4") (pinfunction "4_4") (pintype "passive"))
      (node (ref "ACT_AN7") (pin "4") (pinfunction "4_4") (pintype "passive"))
      (node (ref "ACT_AN9") (pin "4") (pinfunction "4_4") (pintype "passive"))
      (node (ref "ACT_CdCan1") (pin "2") (pinfunction "2_2") (pintype "passive"))
      (node (ref "ACT_CdCan2") (pin "2") (pinfunction "2_2") (pintype "passive"))
      (node (ref "ACT_CdDrTor1") (pin "1") (pinfunction "1_1") (pintype "passive"))
      (node (ref "ACT_CdDrTor2") (pin "1") (pinfunction "1_1") (pintype "passive"))
      (node (ref "ACT_CdMax485") (pin "2") (pinfunction "2_2") (pintype "passive"))
      (node (ref "ACT_CdMax485dif") (pin "2") (pinfunction "2_2") (pintype "passive"))
      (node (ref "ACT_DrTor1") (pin "2") (pinfunction "Vdd_2") (pintype "passive"))
      (node (ref "ACT_DrTor2") (pin "2") (pinfunction "Vdd_2") (pintype "passive"))
      (node (ref "ACT_MAX485") (pin "8") (pinfunction "VCC_8") (pintype "passive"))
      (node (ref "ACT_MAX485dif") (pin "8") (pinfunction "VCC_8") (pintype "passive"))
      (node (ref "ACT_Rmax485B+") (pin "2") (pinfunction "2_2") (pintype "passive"))
      (node (ref "ACT_RpuMAX485") (pin "2") (pinfunction "2_2") (pintype "passive"))
      (node (ref "ACT_RpuMax485dif") (pin "2") (pinfunction "2_2") (pintype "passive"))
      (node (ref "ACT_STM32F4DISCOVERY") (pin "53") (pinfunction "5V_53") (pintype "passive"))
      (node (ref "ACT_STM32F4DISCOVERY") (pin "54") (pinfunction "5V_54") (pintype "passive"))
      (node (ref "ACT_Ucan") (pin "3") (pinfunction "VDD_3") (pintype "power_in"))
      (node (ref "ACT_cod1") (pin "1") (pinfunction "1_1") (pintype "passive"))
      (node (ref "ACT_cod1") (pin "2") (pinfunction "2_2") (pintype "passive"))
      (node (ref "ACT_cod2") (pin "1") (pinfunction "1_1") (pintype "passive"))
      (node (ref "ACT_cod2") (pin "2") (pinfunction "2_2") (pintype "passive"))
    )
    (net (code "67") (name "12V") (class "Default")
      (node (ref "ACT_AX12") (pin "2") (pinfunction "2_2") (pintype "passive"))
      (node (ref "ACT_RX24") (pin "2") (pinfunction "2_2") (pintype "passive"))
    )
    (net (code "68") (name "24V") (class "Default")
      (node (ref "ACT_AN11") (pin "3") (pinfunction "3_3") (pintype "passive"))
      (node (ref "ACT_AN12") (pin "3") (pinfunction "3_3") (pintype "passive"))
      (node (ref "ACT_AN13") (pin "3") (pinfunction "3_3") (pintype "passive"))
      (node (ref "ACT_AN7") (pin "3") (pinfunction "3_3") (pintype "passive"))
      (node (ref "ACT_AN8") (pin "3") (pinfunction "3_3") (pintype "passive"))
      (node (ref "ACT_AN9") (pin "3") (pinfunction "3_3") (pintype "passive"))
      (node (ref "ACT_CdAN11") (pin "2") (pinfunction "2_2") (pintype "passive"))
      (node (ref "ACT_CdAN12") (pin "2") (pinfunction "2_2") (pintype "passive"))
      (node (ref "ACT_CdAN13") (pin "2") (pinfunction "2_2") (pintype "passive"))
      (node (ref "ACT_CdAN7") (pin "2") (pinfunction "2_2") (pintype "passive"))
      (node (ref "ACT_CdAN8") (pin "2") (pinfunction "2_2") (pintype "passive"))
      (node (ref "ACT_CdAN9") (pin "2") (pinfunction "2_2") (pintype "passive"))
      (node (ref "ACT_tor1") (pin "1") (pinfunction "1_1") (pintype "passive"))
      (node (ref "ACT_tor2") (pin "1") (pinfunction "1_1") (pintype "passive"))
    )
    (net (code "69") (name "GND") (class "Default")
      (node (ref "ACT_Ccod1A") (pin "1") (pinfunction "1_1") (pintype "passive"))
      (node (ref "ACT_Ccod1B") (pin "1") (pinfunction "1_1") (pintype "passive"))
      (node (ref "ACT_Ccod2A") (pin "1") (pinfunction "1_1") (pintype "passive"))
      (node (ref "ACT_Ccod2B") (pin "1") (pinfunction "1_1") (pintype "passive"))
      (node (ref "ACT_CdCan1") (pin "1") (pinfunction "1_1") (pintype "passive"))
      (node (ref "ACT_CdCan2") (pin "1") (pinfunction "1_1") (pintype "passive"))
      (node (ref "ACT_CdMax485") (pin "1") (pinfunction "1_1") (pintype "passive"))
      (node (ref "ACT_CdMax485dif") (pin "1") (pinfunction "1_1") (pintype "passive"))
      (node (ref "ACT_CfAn11") (pin "1") (pinfunction "1_1") (pintype "passive"))
      (node (ref "ACT_CfAn12") (pin "1") (pinfunction "1_1") (pintype "passive"))
      (node (ref "ACT_CfAn13") (pin "1") (pinfunction "1_1") (pintype "passive"))
      (node (ref "ACT_CfAn14") (pin "1") (pinfunction "1_1") (pintype "passive"))
      (node (ref "ACT_CfAn15") (pin "1") (pinfunction "1_1") (pintype "passive"))
      (node (ref "ACT_CfAn7") (pin "1") (pinfunction "1_1") (pintype "passive"))
      (node (ref "ACT_CfAn8") (pin "1") (pinfunction "1_1") (pintype "passive"))
      (node (ref "ACT_CfAn9") (pin "1") (pinfunction "1_1") (pintype "passive"))
      (node (ref "ACT_Cu1rx") (pin "1") (pinfunction "1_1") (pintype "passive"))
      (node (ref "ACT_DSelftest") (pin "2") (pinfunction "K_2") (pintype "passive"))
      (node (ref "ACT_Derror") (pin "2") (pinfunction "K_2") (pintype "passive"))
      (node (ref "ACT_MAX485") (pin "5") (pinfunction "GND_5") (pintype "passive"))
      (node (ref "ACT_MAX485dif") (pin "5") (pinfunction "GND_5") (pintype "passive"))
      (node (ref "ACT_RFU") (pin "1") (pinfunction "1_1") (pintype "passive"))
      (node (ref "ACT_RdwnAn11") (pin "1") (pinfunction "1_1") (pintype "passive"))
      (node (ref "ACT_RdwnAn12") (pin "1") (pinfunction "1_1") (pintype "passive"))
      (node (ref "ACT_RdwnAn13") (pin "1") (pinfunction "1_1") (pintype "passive"))
      (node (ref "ACT_RdwnAn7") (pin "1") (pinfunction "1_1") (pintype "passive"))
      (node (ref "ACT_RdwnAn8") (pin "1") (pinfunction "1_1") (pintype "passive"))
      (node (ref "ACT_RdwnAn9") (pin "1") (pinfunction "1_1") (pintype "passive"))
      (node (ref "ACT_RdwnWAmI") (pin "1") (pinfunction "1_1") (pintype "passive"))
      (node (ref "ACT_Rmax485B-") (pin "1") (pinfunction "1_1") (pintype "passive"))
      (node (ref "ACT_RpdDrTor1") (pin "1") (pinfunction "1_1") (pintype "passive"))
      (node (ref "ACT_RpdDrTor2") (pin "1") (pinfunction "1_1") (pintype "passive"))
      (node (ref "ACT_STM32F4DISCOVERY") (pin "1") (pinfunction "GND_1") (pintype "passive"))
      (node (ref "ACT_STM32F4DISCOVERY") (pin "100") (pinfunction "GND_100") (pintype "passive"))
      (node (ref "ACT_STM32F4DISCOVERY") (pin "2") (pinfunction "GND_2") (pintype "passive"))
      (node (ref "ACT_STM32F4DISCOVERY") (pin "23") (pinfunction "GND_23") (pintype "passive"))
      (node (ref "ACT_STM32F4DISCOVERY") (pin "49") (pinfunction "GND_49") (pintype "passive"))
      (node (ref "ACT_STM32F4DISCOVERY") (pin "5") (pinfunction "GND_5") (pintype "passive"))
      (node (ref "ACT_STM32F4DISCOVERY") (pin "50") (pinfunction "GND_50") (pintype "passive"))
      (node (ref "ACT_STM32F4DISCOVERY") (pin "51") (pinfunction "GND_51") (pintype "passive"))
      (node (ref "ACT_STM32F4DISCOVERY") (pin "52") (pinfunction "GND_52") (pintype "passive"))
      (node (ref "ACT_STM32F4DISCOVERY") (pin "99") (pinfunction "GND_99") (pintype "passive"))
      (node (ref "ACT_UART1") (pin "5") (pinfunction "5_5") (pintype "passive"))
      (node (ref "ACT_UART1") (pin "6") (pinfunction "6_6") (pintype "passive"))
      (node (ref "ACT_Ucan") (pin "2") (pinfunction "VSS_2") (pintype "power_in"))
      (node (ref "ACT_Ucan") (pin "8") (pinfunction "RS_8") (pintype "input"))
      (node (ref "ACT__Mot12") (pin "3") (pinfunction "3_3") (pintype "passive"))
      (node (ref "ACT__Mot12") (pin "4") (pinfunction "4_4") (pintype "passive"))
      (node (ref "ACT_cod1") (pin "5") (pinfunction "5_5") (pintype "passive"))
      (node (ref "ACT_cod1") (pin "6") (pinfunction "6_6") (pintype "passive"))
      (node (ref "ACT_cod2") (pin "5") (pinfunction "5_5") (pintype "passive"))
      (node (ref "ACT_cod2") (pin "6") (pinfunction "6_6") (pintype "passive"))
      (node (ref "ACT_currentMot") (pin "1") (pinfunction "1_1") (pintype "passive"))
      (node (ref "ACT_mot34") (pin "3") (pinfunction "3_3") (pintype "passive"))
      (node (ref "ACT_mot34") (pin "4") (pinfunction "4_4") (pintype "passive"))
      (node (ref "ACT_stAN11") (pin "3") (pinfunction "3_3") (pintype "passive"))
      (node (ref "ACT_stAN12") (pin "3") (pinfunction "3_3") (pintype "passive"))
      (node (ref "ACT_stAN13") (pin "3") (pinfunction "3_3") (pintype "passive"))
      (node (ref "ACT_stAN7") (pin "3") (pinfunction "3_3") (pintype "passive"))
      (node (ref "ACT_stAN9") (pin "3") (pinfunction "3_3") (pintype "passive"))
    )
    (net (code "70") (name "GND_12") (class "Default")
      (node (ref "ACT_AX12") (pin "1") (pinfunction "1_1") (pintype "passive"))
      (node (ref "ACT_RX24") (pin "1") (pinfunction "1_1") (pintype "passive"))
    )
    (net (code "71") (name "GND_24") (class "Default")
      (node (ref "ACT_AN8") (pin "1") (pinfunction "1_1") (pintype "passive"))
      (node (ref "ACT_CdAN11") (pin "1") (pinfunction "1_1") (pintype "passive"))
      (node (ref "ACT_CdAN12") (pin "1") (pinfunction "1_1") (pintype "passive"))
      (node (ref "ACT_CdAN13") (pin "1") (pinfunction "1_1") (pintype "passive"))
      (node (ref "ACT_CdAN7") (pin "1") (pinfunction "1_1") (pintype "passive"))
      (node (ref "ACT_CdAN8") (pin "1") (pinfunction "1_1") (pintype "passive"))
      (node (ref "ACT_CdAN9") (pin "1") (pinfunction "1_1") (pintype "passive"))
      (node (ref "ACT_CdDrTor1") (pin "2") (pinfunction "2_2") (pintype "passive"))
      (node (ref "ACT_CdDrTor2") (pin "2") (pinfunction "2_2") (pintype "passive"))
      (node (ref "ACT_DrTor1") (pin "1") (pinfunction "GND_1") (pintype "passive"))
      (node (ref "ACT_DrTor1") (pin "4") (pinfunction "GND_4") (pintype "passive"))
      (node (ref "ACT_DrTor2") (pin "1") (pinfunction "GND_1") (pintype "passive"))
      (node (ref "ACT_DrTor2") (pin "4") (pinfunction "GND_4") (pintype "passive"))
      (node (ref "ACT_Qtor1") (pin "3") (pinfunction "S_3") (pintype "passive"))
      (node (ref "ACT_Qtor2") (pin "3") (pinfunction "S_3") (pintype "passive"))
      (node (ref "ACT_stAN11") (pin "1") (pinfunction "1_1") (pintype "passive"))
      (node (ref "ACT_stAN12") (pin "1") (pinfunction "1_1") (pintype "passive"))
      (node (ref "ACT_stAN13") (pin "1") (pinfunction "1_1") (pintype "passive"))
      (node (ref "ACT_stAN7") (pin "1") (pinfunction "1_1") (pintype "passive"))
      (node (ref "ACT_stAN9") (pin "1") (pinfunction "1_1") (pintype "passive"))
      (node (ref "ACT_tor1") (pin "2") (pinfunction "2_2") (pintype "passive"))
      (node (ref "ACT_tor2") (pin "2") (pinfunction "2_2") (pintype "passive"))
    )
    (net (code "72") (name "Net-(ACT_AN7-Pad1)") (class "Default")
      (node (ref "ACT_AN7") (pin "1") (pinfunction "1_1") (pintype "passive"))
      (node (ref "ACT_stAN7") (pin "2") (pinfunction "2_2") (pintype "passive"))
    )
    (net (code "73") (name "Net-(ACT_AN7-Pad2)") (class "Default")
      (node (ref "ACT_AN7") (pin "2") (pinfunction "2_2") (pintype "passive"))
      (node (ref "ACT_RdwnAn7") (pin "2") (pinfunction "2_2") (pintype "passive"))
      (node (ref "ACT_RfAn7") (pin "2") (pinfunction "2_2") (pintype "passive"))
    )
    (net (code "74") (name "Net-(ACT_AN8-Pad2)") (class "Default")
      (node (ref "ACT_AN8") (pin "2") (pinfunction "2_2") (pintype "passive"))
      (node (ref "ACT_RdwnAn8") (pin "2") (pinfunction "2_2") (pintype "passive"))
      (node (ref "ACT_RfAn8") (pin "2") (pinfunction "2_2") (pintype "passive"))
    )
    (net (code "75") (name "Net-(ACT_AN9-Pad1)") (class "Default")
      (node (ref "ACT_AN9") (pin "1") (pinfunction "1_1") (pintype "passive"))
      (node (ref "ACT_stAN9") (pin "2") (pinfunction "2_2") (pintype "passive"))
    )
    (net (code "76") (name "Net-(ACT_AN9-Pad2)") (class "Default")
      (node (ref "ACT_AN9") (pin "2") (pinfunction "2_2") (pintype "passive"))
      (node (ref "ACT_RdwnAn9") (pin "2") (pinfunction "2_2") (pintype "passive"))
      (node (ref "ACT_RfAn9") (pin "2") (pinfunction "2_2") (pintype "passive"))
    )
    (net (code "77") (name "Net-(ACT_AN11-Pad1)") (class "Default")
      (node (ref "ACT_AN11") (pin "1") (pinfunction "1_1") (pintype "passive"))
      (node (ref "ACT_stAN11") (pin "2") (pinfunction "2_2") (pintype "passive"))
    )
    (net (code "78") (name "Net-(ACT_AN11-Pad2)") (class "Default")
      (node (ref "ACT_AN11") (pin "2") (pinfunction "2_2") (pintype "passive"))
      (node (ref "ACT_RdwnAn11") (pin "2") (pinfunction "2_2") (pintype "passive"))
      (node (ref "ACT_RfAn11") (pin "2") (pinfunction "2_2") (pintype "passive"))
    )
    (net (code "79") (name "Net-(ACT_AN12-Pad1)") (class "Default")
      (node (ref "ACT_AN12") (pin "1") (pinfunction "1_1") (pintype "passive"))
      (node (ref "ACT_stAN12") (pin "2") (pinfunction "2_2") (pintype "passive"))
    )
    (net (code "80") (name "Net-(ACT_AN12-Pad2)") (class "Default")
      (node (ref "ACT_AN12") (pin "2") (pinfunction "2_2") (pintype "passive"))
      (node (ref "ACT_RdwnAn12") (pin "2") (pinfunction "2_2") (pintype "passive"))
      (node (ref "ACT_RfAn12") (pin "2") (pinfunction "2_2") (pintype "passive"))
    )
    (net (code "81") (name "Net-(ACT_AN13-Pad1)") (class "Default")
      (node (ref "ACT_AN13") (pin "1") (pinfunction "1_1") (pintype "passive"))
      (node (ref "ACT_stAN13") (pin "2") (pinfunction "2_2") (pintype "passive"))
    )
    (net (code "82") (name "Net-(ACT_AN13-Pad2)") (class "Default")
      (node (ref "ACT_AN13") (pin "2") (pinfunction "2_2") (pintype "passive"))
      (node (ref "ACT_RdwnAn13") (pin "2") (pinfunction "2_2") (pintype "passive"))
      (node (ref "ACT_RfAn13") (pin "2") (pinfunction "2_2") (pintype "passive"))
    )
    (net (code "83") (name "Net-(ACT_DSelftest-A)") (class "Default")
      (node (ref "ACT_DSelftest") (pin "1") (pinfunction "A_1") (pintype "passive"))
      (node (ref "ACT_Rdselftest") (pin "2") (pinfunction "2_2") (pintype "passive"))
    )
    (net (code "84") (name "Net-(ACT_Derror-A)") (class "Default")
      (node (ref "ACT_Derror") (pin "1") (pinfunction "A_1") (pintype "passive"))
      (node (ref "ACT_Rderror") (pin "2") (pinfunction "2_2") (pintype "passive"))
    )
    (net (code "85") (name "Net-(ACT_DrTor1-OUT)") (class "Default")
      (node (ref "ACT_DrTor1") (pin "5") (pinfunction "OUT_5") (pintype "passive"))
      (node (ref "ACT_Qtor1") (pin "1") (pinfunction "G_1") (pintype "passive"))
    )
    (net (code "86") (name "Net-(ACT_DrTor2-OUT)") (class "Default")
      (node (ref "ACT_DrTor2") (pin "5") (pinfunction "OUT_5") (pintype "passive"))
      (node (ref "ACT_Qtor2") (pin "1") (pinfunction "G_1") (pintype "passive"))
    )
    (net (code "87") (name "Net-(ACT_MAX485-~{B})") (class "Default")
      (node (ref "ACT_MAX485") (pin "7") (pinfunction "~{B}_7") (pintype "bidirectional"))
      (node (ref "ACT_Rmax485B+") (pin "1") (pinfunction "1_1") (pintype "passive"))
      (node (ref "ACT_Rmax485B-") (pin "2") (pinfunction "2_2") (pintype "passive"))
    )
    (net (code "88") (name "Net-(ACT_Qtor1-D)") (class "Default")
      (node (ref "ACT_Qtor1") (pin "2") (pinfunction "D_2") (pintype "passive"))
      (node (ref "ACT_tor1") (pin "3") (pinfunction "3_3") (pintype "passive"))
    )
    (net (code "89") (name "Net-(ACT_Qtor2-D)") (class "Default")
      (node (ref "ACT_Qtor2") (pin "2") (pinfunction "D_2") (pintype "passive"))
      (node (ref "ACT_tor2") (pin "3") (pinfunction "3_3") (pintype "passive"))
    )
    (net (code "90") (name "Net-(ACT_RCod1A-Pad2)") (class "Default")
      (node (ref "ACT_RCod1A") (pin "2") (pinfunction "2_2") (pintype "passive"))
      (node (ref "ACT_cod1") (pin "3") (pinfunction "3_3") (pintype "passive"))
    )
    (net (code "91") (name "Net-(ACT_RCod1B-Pad2)") (class "Default")
      (node (ref "ACT_RCod1B") (pin "2") (pinfunction "2_2") (pintype "passive"))
      (node (ref "ACT_cod1") (pin "4") (pinfunction "4_4") (pintype "passive"))
    )
    (net (code "92") (name "Net-(ACT_RCod2A-Pad2)") (class "Default")
      (node (ref "ACT_RCod2A") (pin "2") (pinfunction "2_2") (pintype "passive"))
      (node (ref "ACT_cod2") (pin "3") (pinfunction "3_3") (pintype "passive"))
    )
    (net (code "93") (name "Net-(ACT_RCod2B-Pad2)") (class "Default")
      (node (ref "ACT_RCod2B") (pin "2") (pinfunction "2_2") (pintype "passive"))
      (node (ref "ACT_cod2") (pin "4") (pinfunction "4_4") (pintype "passive"))
    )
    (net (code "94") (name "Net-(ACT_RfAn14-Pad2)") (class "Default")
      (node (ref "ACT_RfAn14") (pin "2") (pinfunction "2_2") (pintype "passive"))
      (node (ref "ACT_currentMot") (pin "3") (pinfunction "3_3") (pintype "passive"))
    )
    (net (code "95") (name "Net-(ACT_RfAn15-Pad2)") (class "Default")
      (node (ref "ACT_RfAn15") (pin "2") (pinfunction "2_2") (pintype "passive"))
      (node (ref "ACT_currentMot") (pin "2") (pinfunction "2_2") (pintype "passive"))
    )
    (net (code "96") (name "unconnected-(ACT_RFU-Pad4)") (class "Default")
      (node (ref "ACT_RFU") (pin "4") (pinfunction "4_4") (pintype "passive"))
    )
    (net (code "97") (name "unconnected-(ACT_STM32F4DISCOVERY-BOOT0{slash}VPP-Pad71)") (class "Default")
      (node (ref "ACT_STM32F4DISCOVERY") (pin "71") (pinfunction "BOOT0/VPP_71") (pintype "passive+no_connect"))
    )
    (net (code "98") (name "unconnected-(ACT_STM32F4DISCOVERY-NC-Pad48)") (class "Default")
      (node (ref "ACT_STM32F4DISCOVERY") (pin "48") (pinfunction "NC_48") (pintype "passive+no_connect"))
    )
    (net (code "99") (name "unconnected-(ACT_STM32F4DISCOVERY-NRST-Pad6)") (class "Default")
      (node (ref "ACT_STM32F4DISCOVERY") (pin "6") (pinfunction "NRST_6") (pintype "passive+no_connect"))
    )
    (net (code "100") (name "unconnected-(ACT_STM32F4DISCOVERY-PA0-WKUP{slash}USART2_CTS{slash}USART4_TX{slash}ETH_MII_CRS{slash}TIM2_CH1_ETR{slash}TIM5_CH1{slash}TIM8_ETR{slash}ADC123_IN0{slash}WKUP-Pad12)") (class "Default")
      (node (ref "ACT_STM32F4DISCOVERY") (pin "12") (pinfunction "PA0-WKUP/USART2_CTS/USART4_TX/ETH_MII_CRS/TIM2_CH1_ETR/TIM5_CH1/TIM8_ETR/ADC123_IN0/WKUP_12") (pintype "passive+no_connect"))
    )
    (net (code "101") (name "unconnected-(ACT_STM32F4DISCOVERY-PA4{slash}SPI1_NSS{slash}SPI3_NSS{slash}USART2_CK{slash}DCMI_HSYNC{slash}OTG_HS_SOF{slash}I2S3_WS{slash}ADC12_IN4{slash}DAC1_OUT-Pad16)") (class "Default")
      (node (ref "ACT_STM32F4DISCOVERY") (pin "16") (pinfunction "PA4/SPI1_NSS/SPI3_NSS/USART2_CK/DCMI_HSYNC/OTG_HS_SOF/I2S3_WS/ADC12_IN4/DAC1_OUT_16") (pintype "passive+no_connect"))
    )
    (net (code "102") (name "unconnected-(ACT_STM32F4DISCOVERY-PA6{slash}SPI1_MISO{slash}TIM8_BKIN{slash}TIM13_CH1{slash}DCMI_PIXCLK{slash}TIM3_CH1{slash}TIM1_BKIN{slash}ADC12_IN6-Pad18)") (class "Default")
      (node (ref "ACT_STM32F4DISCOVERY") (pin "18") (pinfunction "PA6/SPI1_MISO/TIM8_BKIN/TIM13_CH1/DCMI_PIXCLK/TIM3_CH1/TIM1_BKIN/ADC12_IN6_18") (pintype "passive+no_connect"))
    )
    (net (code "103") (name "unconnected-(ACT_STM32F4DISCOVERY-PA9{slash}USART1_TX{slash}TIM1_CH2{slash}I2C3_SMBA{slash}DCMI_D0{slash}OTG_FS_VBUS-Pad94)") (class "Default")
      (node (ref "ACT_STM32F4DISCOVERY") (pin "94") (pinfunction "PA9/USART1_TX/TIM1_CH2/I2C3_SMBA/DCMI_D0/OTG_FS_VBUS_94") (pintype "passive+no_connect"))
    )
    (net (code "104") (name "unconnected-(ACT_STM32F4DISCOVERY-PA10{slash}USART1_RX{slash}TIM1_CH3{slash}OTG_FS_ID{slash}DCMI_D1-Pad91)") (class "Default")
      (node (ref "ACT_STM32F4DISCOVERY") (pin "91") (pinfunction "PA10/USART1_RX/TIM1_CH3/OTG_FS_ID/DCMI_D1_91") (pintype "passive+no_connect"))
    )
    (net (code "105") (name "unconnected-(ACT_STM32F4DISCOVERY-PA13{slash}JTMS_SWDIO-Pad92)") (class "Default")
      (node (ref "ACT_STM32F4DISCOVERY") (pin "92") (pinfunction "PA13/JTMS_SWDIO_92") (pintype "passive+no_connect"))
    )
    (net (code "106") (name "unconnected-(ACT_STM32F4DISCOVERY-PA14{slash}JTCK_SWCLK-Pad89)") (class "Default")
      (node (ref "ACT_STM32F4DISCOVERY") (pin "89") (pinfunction "PA14/JTCK_SWCLK_89") (pintype "passive+no_connect"))
    )
    (net (code "107") (name "unconnected-(ACT_STM32F4DISCOVERY-PB3{slash}JTDO{slash}TRACESWO{slash}SPI3_SCK{slash}I2S3_CK{slash}TIM2_CH2{slash}SPI1_SCK-Pad78)") (class "Default")
      (node (ref "ACT_STM32F4DISCOVERY") (pin "78") (pinfunction "PB3/JTDO/TRACESWO/SPI3_SCK/I2S3_CK/TIM2_CH2/SPI1_SCK_78") (pintype "passive+no_connect"))
    )
    (net (code "108") (name "unconnected-(ACT_STM32F4DISCOVERY-PB8{slash}TIM4_CH3{slash}SDIO_D4{slash}TIM10_CH1{slash}DCMI_D6{slash}OTG_FS_SCL{slash}ETH_MII_TXD3{slash}I2C1_SCL{slash}CAN1_RX-Pad69)") (class "Default")
      (node (ref "ACT_STM32F4DISCOVERY") (pin "69") (pinfunction "PB8/TIM4_CH3/SDIO_D4/TIM10_CH1/DCMI_D6/OTG_FS_SCL/ETH_MII_TXD3/I2C1_SCL/CAN1_RX_69") (pintype "passive+no_connect"))
    )
    (net (code "109") (name "unconnected-(ACT_STM32F4DISCOVERY-PC0{slash}OTG_HS_ULPI_STP{slash}ADC123_IN10-Pad8)") (class "Default")
      (node (ref "ACT_STM32F4DISCOVERY") (pin "8") (pinfunction "PC0/OTG_HS_ULPI_STP/ADC123_IN10_8") (pintype "passive+no_connect"))
    )
    (net (code "110") (name "unconnected-(ACT_STM32F4DISCOVERY-PC14{slash}OSC32_IN-Pad59)") (class "Default")
      (node (ref "ACT_STM32F4DISCOVERY") (pin "59") (pinfunction "PC14/OSC32_IN_59") (pintype "passive+no_connect"))
    )
    (net (code "111") (name "unconnected-(ACT_STM32F4DISCOVERY-PC15{slash}OSC32_OUT-Pad60)") (class "Default")
      (node (ref "ACT_STM32F4DISCOVERY") (pin "60") (pinfunction "PC15/OSC32_OUT_60") (pintype "passive+no_connect"))
    )
    (net (code "112") (name "unconnected-(ACT_STM32F4DISCOVERY-PD4{slash}FSMC_NOE{slash}USART2_RTS-Pad82)") (class "Default")
      (node (ref "ACT_STM32F4DISCOVERY") (pin "82") (pinfunction "PD4/FSMC_NOE/USART2_RTS_82") (pintype "passive+no_connect"))
    )
    (net (code "113") (name "unconnected-(ACT_STM32F4DISCOVERY-PD5{slash}FSMC_NWE{slash}USART2_TX-Pad79)") (class "Default")
      (node (ref "ACT_STM32F4DISCOVERY") (pin "79") (pinfunction "PD5/FSMC_NWE/USART2_TX_79") (pintype "passive+no_connect"))
    )
    (net (code "114") (name "unconnected-(ACT_STM32F4DISCOVERY-PE0{slash}TIM4_ETR{slash}FSMC_NBL0{slash}DCMI_D2-Pad67)") (class "Default")
      (node (ref "ACT_STM32F4DISCOVERY") (pin "67") (pinfunction "PE0/TIM4_ETR/FSMC_NBL0/DCMI_D2_67") (pintype "passive+no_connect"))
    )
    (net (code "115") (name "unconnected-(ACT_STM32F4DISCOVERY-PE1{slash}FSMC_NBL1{slash}DCMI_D3-Pad68)") (class "Default")
      (node (ref "ACT_STM32F4DISCOVERY") (pin "68") (pinfunction "PE1/FSMC_NBL1/DCMI_D3_68") (pintype "passive+no_connect"))
    )
    (net (code "116") (name "unconnected-(ACT_STM32F4DISCOVERY-PE2{slash}TRACECLK{slash}FSMC_A23{slash}ETH_MII_TXD3-Pad65)") (class "Default")
      (node (ref "ACT_STM32F4DISCOVERY") (pin "65") (pinfunction "PE2/TRACECLK/FSMC_A23/ETH_MII_TXD3_65") (pintype "passive+no_connect"))
    )
    (net (code "117") (name "unconnected-(ACT_STM32F4DISCOVERY-PE3{slash}TRACED0{slash}FSMC_A19-Pad66)") (class "Default")
      (node (ref "ACT_STM32F4DISCOVERY") (pin "66") (pinfunction "PE3/TRACED0/FSMC_A19_66") (pintype "passive+no_connect"))
    )
    (net (code "118") (name "unconnected-(ACT_STM32F4DISCOVERY-PE4{slash}TRACED1{slash}FSMC_A20{slash}DCMI_D4-Pad63)") (class "Default")
      (node (ref "ACT_STM32F4DISCOVERY") (pin "63") (pinfunction "PE4/TRACED1/FSMC_A20/DCMI_D4_63") (pintype "passive+no_connect"))
    )
    (net (code "119") (name "unconnected-(ACT_STM32F4DISCOVERY-PE5{slash}TRACED2{slash}FSMC_A21{slash}TIM9_CH1{slash}DCMI_D6-Pad64)") (class "Default")
      (node (ref "ACT_STM32F4DISCOVERY") (pin "64") (pinfunction "PE5/TRACED2/FSMC_A21/TIM9_CH1/DCMI_D6_64") (pintype "passive+no_connect"))
    )
    (net (code "120") (name "unconnected-(ACT_STM32F4DISCOVERY-PE6{slash}TRACED3{slash}FSMC_A22{slash}TIM9_CH2{slash}DCMI_D7-Pad61)") (class "Default")
      (node (ref "ACT_STM32F4DISCOVERY") (pin "61") (pinfunction "PE6/TRACED3/FSMC_A22/TIM9_CH2/DCMI_D7_61") (pintype "passive+no_connect"))
    )
    (net (code "121") (name "unconnected-(ACT_STM32F4DISCOVERY-PH0{slash}OSC_IN-Pad57)") (class "Default")
      (node (ref "ACT_STM32F4DISCOVERY") (pin "57") (pinfunction "PH0/OSC_IN_57") (pintype "passive+no_connect"))
    )
    (net (code "122") (name "unconnected-(ACT_STM32F4DISCOVERY-PH1{slash}OSC_OUT-Pad58)") (class "Default")
      (node (ref "ACT_STM32F4DISCOVERY") (pin "58") (pinfunction "PH1/OSC_OUT_58") (pintype "passive+no_connect"))
    )
    (net (code "123") (name "unconnected-(ACT_STM32F4DISCOVERY-VDD-Pad3)") (class "Default")
      (node (ref "ACT_STM32F4DISCOVERY") (pin "3") (pinfunction "VDD_3") (pintype "passive+no_connect"))
    )
    (net (code "124") (name "unconnected-(ACT_STM32F4DISCOVERY-VDD-Pad4)") (class "Default")
      (node (ref "ACT_STM32F4DISCOVERY") (pin "4") (pinfunction "VDD_4") (pintype "passive+no_connect"))
    )
    (net (code "125") (name "unconnected-(ACT_STM32F4DISCOVERY-VDD-Pad72)") (class "Default")
      (node (ref "ACT_STM32F4DISCOVERY") (pin "72") (pinfunction "VDD_72") (pintype "passive+no_connect"))
    )
    (net (code "126") (name "unconnected-(ACT_UART1-Pad1)") (class "Default")
      (node (ref "ACT_UART1") (pin "1") (pinfunction "1_1") (pintype "passive+no_connect"))
    )
    (net (code "127") (name "unconnected-(ACT_UART1-Pad2)") (class "Default")
      (node (ref "ACT_UART1") (pin "2") (pinfunction "2_2") (pintype "passive+no_connect"))
    )
    (net (code "128") (name "unconnected-(ACT_Ucan-VREF-Pad5)") (class "Default")
      (node (ref "ACT_Ucan") (pin "5") (pinfunction "VREF_5") (pintype "output"))
    )
  )
)
